# Hypnos_V3.net
KiCad netlist of a schematic drawn in EAGLE
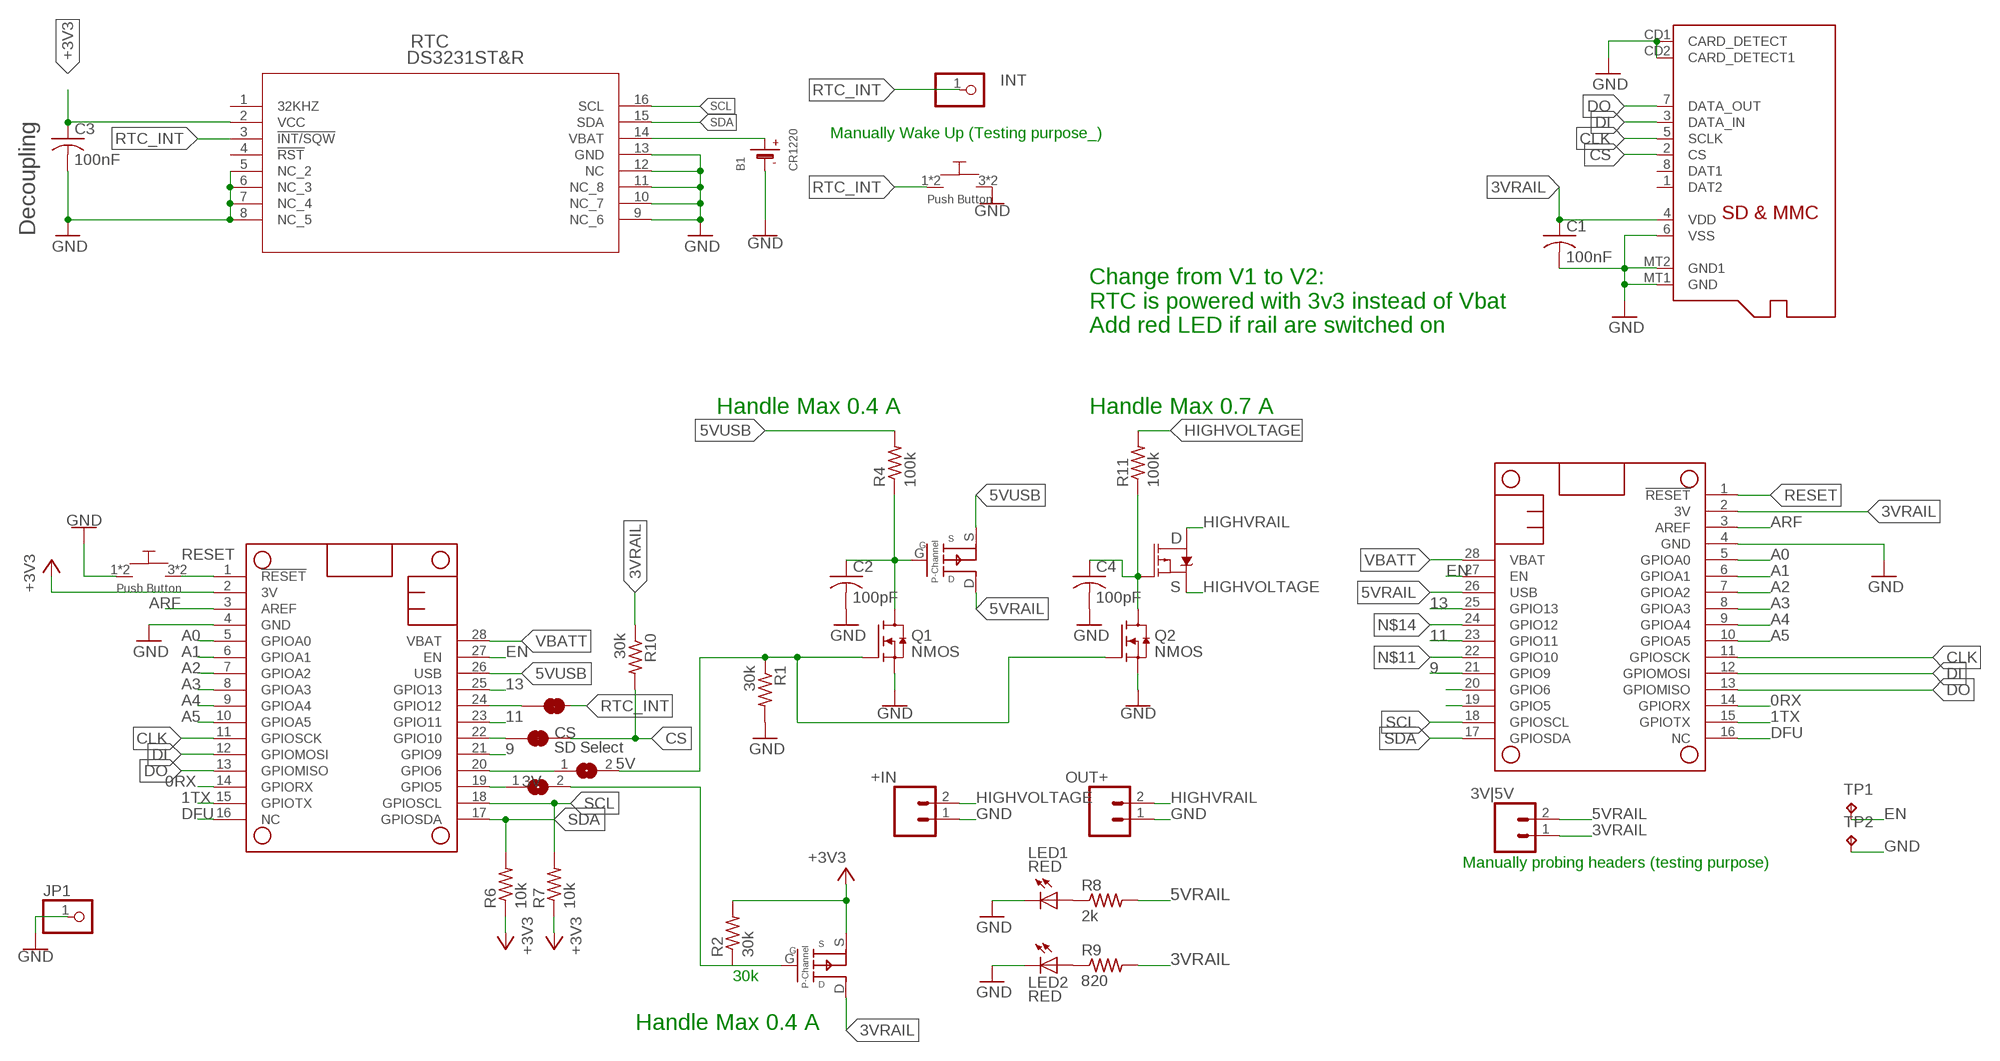
[diagram p0: schematic, sheet 1]

(export (version "E")
  (design (tool "Eeschema 10.0.6"))
  (components
    (comp (ref "+IN")
      (value "HIGHV-IN")
      (footprint "eagle-import:1X02_NO_SILK")
      (libsource (lib "eagle-import") (part "CONN_021X02_NO_SILK"))
    )
    (comp (ref "3V") (value "SJ") (footprint "eagle-import:SJ") (libsource (lib "eagle-import") (part "SJ")))
    (comp (ref "3V|5V")
      (value "CONN_021X02_NO_SILK")
      (footprint "eagle-import:1X02_NO_SILK")
      (libsource (lib "eagle-import") (part "CONN_021X02_NO_SILK"))
    )
    (comp (ref "5V") (value "SJ") (footprint "eagle-import:SJ") (libsource (lib "eagle-import") (part "SJ")))
    (comp (ref "B1")
      (value "CR1220")
      (footprint "eagle-import:CR1220")
      (libsource (lib "eagle-import") (part "BATTERYCR1220_SMT"))
    )
    (comp (ref "C1")
      (value "100nF")
      (footprint "eagle-import:C1206")
      (libsource (lib "eagle-import") (part "C-USC1206"))
    )
    (comp (ref "C2")
      (value "100pF")
      (footprint "eagle-import:C0805")
      (libsource (lib "eagle-import") (part "resistor_348_C-USC0805"))
    )
    (comp (ref "C3")
      (value "100nF")
      (footprint "eagle-import:C1206")
      (libsource (lib "eagle-import") (part "C-USC1206"))
    )
    (comp (ref "C4")
      (value "100pF")
      (footprint "eagle-import:C0805")
      (libsource (lib "eagle-import") (part "resistor_348_C-USC0805"))
    )
    (comp (ref "CS")
      (value "SD Select")
      (footprint "eagle-import:SMT-JUMPER_2_NC_TRACE_SILK")
      (libsource (lib "eagle-import") (part "JUMPER-SMT_2_NC_TRACE_SILK"))
    )
    (comp (ref "INT")
      (value "PINHD-1X1CB")
      (footprint "eagle-import:1X01-CLEANBIG")
      (libsource (lib "eagle-import") (part "PINHD-1X1CB"))
    )
    (comp (ref "JP1")
      (value "PINHD-1X1CB")
      (footprint "eagle-import:1X01-CLEANBIG")
      (libsource (lib "eagle-import") (part "PINHD-1X1CB"))
    )
    (comp (ref "LED1")
      (value "RED")
      (footprint "eagle-import:CHIPLED_0805")
      (libsource (lib "eagle-import") (part "LEDCHIPLED_0805"))
    )
    (comp (ref "LED2")
      (value "RED")
      (footprint "eagle-import:CHIPLED_0805")
      (libsource (lib "eagle-import") (part "LEDCHIPLED_0805"))
    )
    (comp (ref "MICROSD")
      (value "MICROSD")
      (footprint "eagle-import:MICROSD")
      (libsource (lib "eagle-import") (part "MICROSD"))
    )
    (comp (ref "MS1")
      (value "FEATHERWING")
      (footprint "eagle-import:FEATHERWING")
      (libsource (lib "eagle-import") (part "powerboard_FEATHERWING"))
    )
    (comp (ref "MS2")
      (value "FEATHERWING")
      (footprint "eagle-import:FEATHERWING")
      (libsource (lib "eagle-import") (part "FEATHERWING"))
    )
    (comp (ref "OUT+")
      (value "HIGHV-OUT")
      (footprint "eagle-import:1X02_NO_SILK")
      (libsource (lib "eagle-import") (part "CONN_021X02_NO_SILK"))
    )
    (comp (ref "PMOS1")
      (value "SSM3J3228R")
      (footprint "eagle-import:SOT-23-3")
      (libsource (lib "eagle-import") (part "SSM3J3228R"))
    )
    (comp (ref "PMOS2")
      (value "SSM3J3228R")
      (footprint "eagle-import:SOT-23-3")
      (libsource (lib "eagle-import") (part "SSM3J3228R"))
    )
    (comp (ref "PMOS3")
      (value "P-MOSFET")
      (footprint "eagle-import:SOT23-6")
      (libsource (lib "eagle-import") (part "P-MOSFET"))
    )
    (comp (ref "Q1")
      (value "NMOS")
      (footprint "eagle-import:SOT23-S")
      (libsource (lib "eagle-import") (part "NMOS"))
    )
    (comp (ref "Q2")
      (value "NMOS")
      (footprint "eagle-import:SOT23-S")
      (libsource (lib "eagle-import") (part "NMOS"))
    )
    (comp (ref "R1")
      (value "30k")
      (footprint "eagle-import:RES_1206")
      (fields
        (field (name "DIGIKEY_PART_NUMBER") "WSLP-.05TR-ND")
        (field (name "MANUFACTURER") "Vishay Dale")
        (field (name "MPN") "WSLP1206R0500FEA")
        (field (name "CREATED_BY") "PCBLayout.com")
      )
      (libsource (lib "eagle-import") (part "WSLP1206R0500FEA"))
    )
    (comp (ref "R2")
      (value "30k")
      (footprint "eagle-import:RES_1206")
      (fields
        (field (name "DIGIKEY_PART_NUMBER") "WSLP-.05TR-ND")
        (field (name "MANUFACTURER") "Vishay Dale")
        (field (name "MPN") "WSLP1206R0500FEA")
        (field (name "CREATED_BY") "PCBLayout.com")
      )
      (libsource (lib "eagle-import") (part "WSLP1206R0500FEA"))
    )
    (comp (ref "R4")
      (value "100k")
      (footprint "eagle-import:RES_1206")
      (fields
        (field (name "DIGIKEY_PART_NUMBER") "WSLP-.05TR-ND")
        (field (name "MANUFACTURER") "Vishay Dale")
        (field (name "MPN") "WSLP1206R0500FEA")
        (field (name "CREATED_BY") "PCBLayout.com")
      )
      (libsource (lib "eagle-import") (part "WSLP1206R0500FEA"))
    )
    (comp (ref "R6")
      (value "10k")
      (footprint "eagle-import:RES_1206")
      (fields
        (field (name "DIGIKEY_PART_NUMBER") "WSLP-.05TR-ND")
        (field (name "MANUFACTURER") "Vishay Dale")
        (field (name "MPN") "WSLP1206R0500FEA")
        (field (name "CREATED_BY") "PCBLayout.com")
      )
      (libsource (lib "eagle-import") (part "WSLP1206R0500FEA"))
    )
    (comp (ref "R7")
      (value "10k")
      (footprint "eagle-import:RES_1206")
      (fields
        (field (name "DIGIKEY_PART_NUMBER") "WSLP-.05TR-ND")
        (field (name "MANUFACTURER") "Vishay Dale")
        (field (name "MPN") "WSLP1206R0500FEA")
        (field (name "CREATED_BY") "PCBLayout.com")
      )
      (libsource (lib "eagle-import") (part "WSLP1206R0500FEA"))
    )
    (comp (ref "R8")
      (value "2k")
      (footprint "eagle-import:RES_1206")
      (fields
        (field (name "DIGIKEY_PART_NUMBER") "WSLP-.05TR-ND")
        (field (name "MANUFACTURER") "Vishay Dale")
        (field (name "MPN") "WSLP1206R0500FEA")
        (field (name "CREATED_BY") "PCBLayout.com")
      )
      (libsource (lib "eagle-import") (part "WSLP1206R0500FEA"))
    )
    (comp (ref "R9")
      (value "820")
      (footprint "eagle-import:RES_1206")
      (fields
        (field (name "DIGIKEY_PART_NUMBER") "WSLP-.05TR-ND")
        (field (name "MANUFACTURER") "Vishay Dale")
        (field (name "MPN") "WSLP1206R0500FEA")
        (field (name "CREATED_BY") "PCBLayout.com")
      )
      (libsource (lib "eagle-import") (part "WSLP1206R0500FEA"))
    )
    (comp (ref "R10")
      (value "30k")
      (footprint "eagle-import:RES_1206")
      (fields
        (field (name "DIGIKEY_PART_NUMBER") "WSLP-.05TR-ND")
        (field (name "MANUFACTURER") "Vishay Dale")
        (field (name "MPN") "WSLP1206R0500FEA")
        (field (name "CREATED_BY") "PCBLayout.com")
      )
      (libsource (lib "eagle-import") (part "WSLP1206R0500FEA"))
    )
    (comp (ref "R11")
      (value "100k")
      (footprint "eagle-import:RES_1206")
      (fields
        (field (name "DIGIKEY_PART_NUMBER") "WSLP-.05TR-ND")
        (field (name "MANUFACTURER") "Vishay Dale")
        (field (name "MPN") "WSLP1206R0500FEA")
        (field (name "CREATED_BY") "PCBLayout.com")
      )
      (libsource (lib "eagle-import") (part "WSLP1206R0500FEA"))
    )
    (comp (ref "RTC")
      (value "DS3231ST&R")
      (footprint "eagle-import:21-0042B_16")
      (fields (field (name "MANUFACTURER_PART_NUMBER") "DS3231S#T&R"))
      (libsource (lib "eagle-import") (part "DS3231ST&R"))
    )
    (comp (ref "RTC_INT")
      (value "JUMPER-SMT_2_NC_TRACE_SILK")
      (footprint "eagle-import:SMT-JUMPER_2_NC_TRACE_SILK")
      (libsource (lib "eagle-import") (part "JUMPER-SMT_2_NC_TRACE_SILK"))
    )
    (comp (ref "TP1")
      (value "TPTP16R")
      (footprint "eagle-import:TP16R")
      (libsource (lib "eagle-import") (part "TPTP16R"))
    )
    (comp (ref "TP2")
      (value "TPTP16R")
      (footprint "eagle-import:TP16R")
      (libsource (lib "eagle-import") (part "TPTP16R"))
    )
    (comp (ref "U$1")
      (value "PUSH_BUTTON")
      (footprint "eagle-import:PUSHBUTTON_SMD")
      (libsource (lib "eagle-import") (part "PUSH_BUTTON"))
    )
    (comp (ref "U$2")
      (value "PUSH_BUTTON")
      (footprint "eagle-import:PUSHBUTTON_SMD")
      (libsource (lib "eagle-import") (part "PUSH_BUTTON"))
    )
  )
  (nets
    (net (code "1") (name "+3V3") (class "Default")
      (node (ref "C3") (pin "1") (pinfunction "1_1") (pintype "passive"))
      (node (ref "MS2") (pin "2") (pinfunction "3V_2") (pintype "power_in"))
      (node (ref "PMOS2") (pin "S") (pinfunction "S_S") (pintype "bidirectional"))
      (node (ref "R2") (pin "2") (pinfunction "2_2") (pintype "passive"))
      (node (ref "R6") (pin "1") (pinfunction "1_1") (pintype "passive"))
      (node (ref "R7") (pin "1") (pinfunction "1_1") (pintype "passive"))
      (node (ref "RTC") (pin "2") (pinfunction "VCC_2") (pintype "power_in"))
    )
    (net (code "2") (name "/0RX") (class "Default")
      (node (ref "MS1") (pin "14") (pinfunction "GPIORX_14") (pintype "bidirectional"))
      (node (ref "MS2") (pin "14") (pinfunction "GPIORX_14") (pintype "bidirectional"))
    )
    (net (code "3") (name "/1TX") (class "Default")
      (node (ref "MS1") (pin "15") (pinfunction "GPIOTX_15") (pintype "bidirectional"))
      (node (ref "MS2") (pin "15") (pinfunction "GPIOTX_15") (pintype "bidirectional"))
    )
    (net (code "4") (name "/9") (class "Default")
      (node (ref "MS1") (pin "21") (pinfunction "GPIO9_21") (pintype "bidirectional"))
      (node (ref "MS2") (pin "21") (pinfunction "GPIO9_21") (pintype "bidirectional"))
    )
    (net (code "5") (name "/11") (class "Default")
      (node (ref "MS1") (pin "23") (pinfunction "GPIO11_23") (pintype "bidirectional"))
      (node (ref "MS2") (pin "23") (pinfunction "GPIO11_23") (pintype "bidirectional"))
    )
    (net (code "6") (name "/13") (class "Default")
      (node (ref "MS1") (pin "25") (pinfunction "GPIO13_25") (pintype "bidirectional"))
      (node (ref "MS2") (pin "25") (pinfunction "GPIO13_25") (pintype "bidirectional"))
    )
    (net (code "7") (name "/A0") (class "Default")
      (node (ref "MS1") (pin "5") (pinfunction "GPIOA0_5") (pintype "bidirectional"))
      (node (ref "MS2") (pin "5") (pinfunction "GPIOA0_5") (pintype "bidirectional"))
    )
    (net (code "8") (name "/A1") (class "Default")
      (node (ref "MS1") (pin "6") (pinfunction "GPIOA1_6") (pintype "bidirectional"))
      (node (ref "MS2") (pin "6") (pinfunction "GPIOA1_6") (pintype "bidirectional"))
    )
    (net (code "9") (name "/A2") (class "Default")
      (node (ref "MS1") (pin "7") (pinfunction "GPIOA2_7") (pintype "bidirectional"))
      (node (ref "MS2") (pin "7") (pinfunction "GPIOA2_7") (pintype "bidirectional"))
    )
    (net (code "10") (name "/A3") (class "Default")
      (node (ref "MS1") (pin "8") (pinfunction "GPIOA3_8") (pintype "bidirectional"))
      (node (ref "MS2") (pin "8") (pinfunction "GPIOA3_8") (pintype "bidirectional"))
    )
    (net (code "11") (name "/A4") (class "Default")
      (node (ref "MS1") (pin "9") (pinfunction "GPIOA4_9") (pintype "bidirectional"))
      (node (ref "MS2") (pin "9") (pinfunction "GPIOA4_9") (pintype "bidirectional"))
    )
    (net (code "12") (name "/A5") (class "Default")
      (node (ref "MS1") (pin "10") (pinfunction "GPIOA5_10") (pintype "bidirectional"))
      (node (ref "MS2") (pin "10") (pinfunction "GPIOA5_10") (pintype "bidirectional"))
    )
    (net (code "13") (name "/ARF") (class "Default")
      (node (ref "MS1") (pin "3") (pinfunction "AREF_3") (pintype "passive"))
      (node (ref "MS2") (pin "3") (pinfunction "AREF_3") (pintype "passive"))
    )
    (net (code "14") (name "/DFU") (class "Default")
      (node (ref "MS1") (pin "16") (pinfunction "NC_16") (pintype "passive"))
      (node (ref "MS2") (pin "16") (pinfunction "NC_16") (pintype "passive"))
    )
    (net (code "15") (name "/EN") (class "Default")
      (node (ref "MS1") (pin "27") (pinfunction "EN_27") (pintype "passive"))
      (node (ref "MS2") (pin "27") (pinfunction "EN_27") (pintype "passive"))
      (node (ref "TP1") (pin "TP") (pinfunction "TP_TP") (pintype "input"))
    )
    (net (code "16") (name "/HIGHVRAIL") (class "Default")
      (node (ref "OUT+") (pin "2") (pinfunction "2_2") (pintype "passive"))
      (node (ref "PMOS3") (pin "1") (pinfunction "D_1") (pintype "bidirectional"))
      (node (ref "PMOS3") (pin "2") (pinfunction "D_2") (pintype "bidirectional"))
      (node (ref "PMOS3") (pin "5") (pinfunction "D_5") (pintype "bidirectional"))
      (node (ref "PMOS3") (pin "6") (pinfunction "D_6") (pintype "bidirectional"))
    )
    (net (code "17") (name "3VRAIL") (class "Default")
      (node (ref "3V|5V") (pin "1") (pinfunction "1_1") (pintype "passive"))
      (node (ref "C1") (pin "1") (pinfunction "1_1") (pintype "passive"))
      (node (ref "MICROSD") (pin "4") (pinfunction "VDD_4") (pintype "power_in"))
      (node (ref "MS1") (pin "2") (pinfunction "3V_2") (pintype "power_in"))
      (node (ref "PMOS2") (pin "D") (pinfunction "D_D") (pintype "bidirectional"))
      (node (ref "R10") (pin "1") (pinfunction "1_1") (pintype "passive"))
      (node (ref "R9") (pin "2") (pinfunction "2_2") (pintype "passive"))
    )
    (net (code "18") (name "5VRAIL") (class "Default")
      (node (ref "3V|5V") (pin "2") (pinfunction "2_2") (pintype "passive"))
      (node (ref "MS1") (pin "26") (pinfunction "USB_26") (pintype "power_in"))
      (node (ref "PMOS1") (pin "D") (pinfunction "D_D") (pintype "bidirectional"))
      (node (ref "R8") (pin "2") (pinfunction "2_2") (pintype "passive"))
    )
    (net (code "19") (name "5VUSB") (class "Default")
      (node (ref "MS2") (pin "26") (pinfunction "USB_26") (pintype "power_in"))
      (node (ref "PMOS1") (pin "S") (pinfunction "S_S") (pintype "bidirectional"))
      (node (ref "R4") (pin "2") (pinfunction "2_2") (pintype "passive"))
    )
    (net (code "20") (name "CLK") (class "Default")
      (node (ref "MICROSD") (pin "5") (pinfunction "SCLK_5") (pintype "input"))
      (node (ref "MS1") (pin "11") (pinfunction "GPIOSCK_11") (pintype "bidirectional"))
      (node (ref "MS2") (pin "11") (pinfunction "GPIOSCK_11") (pintype "bidirectional"))
    )
    (net (code "21") (name "CS") (class "Default")
      (node (ref "CS") (pin "2") (pinfunction "2_2") (pintype "passive"))
      (node (ref "MICROSD") (pin "2") (pinfunction "CS_2") (pintype "input"))
      (node (ref "R10") (pin "2") (pinfunction "2_2") (pintype "passive"))
    )
    (net (code "22") (name "DI") (class "Default")
      (node (ref "MICROSD") (pin "3") (pinfunction "DATA_IN_3") (pintype "input"))
      (node (ref "MS1") (pin "12") (pinfunction "GPIOMOSI_12") (pintype "bidirectional"))
      (node (ref "MS2") (pin "12") (pinfunction "GPIOMOSI_12") (pintype "bidirectional"))
    )
    (net (code "23") (name "DO") (class "Default")
      (node (ref "MICROSD") (pin "7") (pinfunction "DATA_OUT_7") (pintype "output"))
      (node (ref "MS1") (pin "13") (pinfunction "GPIOMISO_13") (pintype "bidirectional"))
      (node (ref "MS2") (pin "13") (pinfunction "GPIOMISO_13") (pintype "bidirectional"))
    )
    (net (code "24") (name "GND") (class "Default")
      (node (ref "+IN") (pin "1") (pinfunction "1_1") (pintype "passive"))
      (node (ref "B1") (pin "-") (pinfunction "-_-") (pintype "passive"))
      (node (ref "C1") (pin "2") (pinfunction "2_2") (pintype "passive"))
      (node (ref "C2") (pin "2") (pinfunction "2_2") (pintype "passive"))
      (node (ref "C3") (pin "2") (pinfunction "2_2") (pintype "passive"))
      (node (ref "C4") (pin "2") (pinfunction "2_2") (pintype "passive"))
      (node (ref "JP1") (pin "1") (pinfunction "1_1") (pintype "passive"))
      (node (ref "LED1") (pin "C") (pinfunction "C_C") (pintype "passive"))
      (node (ref "LED2") (pin "C") (pinfunction "C_C") (pintype "passive"))
      (node (ref "MICROSD") (pin "6") (pinfunction "VSS_6") (pintype "power_in"))
      (node (ref "MICROSD") (pin "CD1") (pinfunction "CARD_DETECT_CD1") (pintype "passive"))
      (node (ref "MICROSD") (pin "CD2") (pinfunction "CARD_DETECT1_CD2") (pintype "passive"))
      (node (ref "MICROSD") (pin "MT1") (pinfunction "GND_MT1") (pintype "power_in"))
      (node (ref "MICROSD") (pin "MT2") (pinfunction "GND1_MT2") (pintype "power_in"))
      (node (ref "MS1") (pin "4") (pinfunction "GND_4") (pintype "power_in"))
      (node (ref "MS2") (pin "4") (pinfunction "GND_4") (pintype "power_in"))
      (node (ref "OUT+") (pin "1") (pinfunction "1_1") (pintype "passive"))
      (node (ref "Q1") (pin "2") (pinfunction "S_2") (pintype "passive"))
      (node (ref "Q2") (pin "2") (pinfunction "S_2") (pintype "passive"))
      (node (ref "R1") (pin "2") (pinfunction "2_2") (pintype "passive"))
      (node (ref "RTC") (pin "10") (pinfunction "NC_7_10") (pintype "passive"))
      (node (ref "RTC") (pin "11") (pinfunction "NC_8_11") (pintype "passive"))
      (node (ref "RTC") (pin "12") (pinfunction "NC_12") (pintype "passive"))
      (node (ref "RTC") (pin "13") (pinfunction "GND_13") (pintype "power_in"))
      (node (ref "RTC") (pin "5") (pinfunction "NC_2_5") (pintype "passive"))
      (node (ref "RTC") (pin "6") (pinfunction "NC_3_6") (pintype "passive"))
      (node (ref "RTC") (pin "7") (pinfunction "NC_4_7") (pintype "passive"))
      (node (ref "RTC") (pin "8") (pinfunction "NC_5_8") (pintype "passive"))
      (node (ref "RTC") (pin "9") (pinfunction "NC_6_9") (pintype "passive"))
      (node (ref "TP2") (pin "TP") (pinfunction "TP_TP") (pintype "input"))
      (node (ref "U$1") (pin "1") (pinfunction "P$1_1") (pintype "bidirectional"))
      (node (ref "U$1") (pin "2") (pinfunction "P$1_2") (pintype "bidirectional"))
      (node (ref "U$2") (pin "3") (pinfunction "P$2_3") (pintype "bidirectional"))
      (node (ref "U$2") (pin "4") (pinfunction "P$2_4") (pintype "bidirectional"))
    )
    (net (code "25") (name "HIGHVOLTAGE") (class "Default")
      (node (ref "+IN") (pin "2") (pinfunction "2_2") (pintype "passive"))
      (node (ref "PMOS3") (pin "4") (pinfunction "S_4") (pintype "bidirectional"))
      (node (ref "R11") (pin "2") (pinfunction "2_2") (pintype "passive"))
    )
    (net (code "26") (name "N$11") (class "Default")
      (node (ref "CS") (pin "1") (pinfunction "1_1") (pintype "passive"))
      (node (ref "MS1") (pin "22") (pinfunction "GPIO10_22") (pintype "bidirectional"))
      (node (ref "MS2") (pin "22") (pinfunction "GPIO10_22") (pintype "bidirectional"))
    )
    (net (code "27") (name "N$14") (class "Default")
      (node (ref "MS1") (pin "24") (pinfunction "GPIO12_24") (pintype "bidirectional"))
      (node (ref "MS2") (pin "24") (pinfunction "GPIO12_24") (pintype "bidirectional"))
      (node (ref "RTC_INT") (pin "1") (pinfunction "1_1") (pintype "passive"))
    )
    (net (code "28") (name "Net-(3V-Pad2)") (class "Default")
      (node (ref "3V") (pin "2") (pinfunction "2_2") (pintype "passive"))
      (node (ref "PMOS2") (pin "G") (pinfunction "G_G") (pintype "bidirectional"))
      (node (ref "R2") (pin "1") (pinfunction "1_1") (pintype "passive"))
    )
    (net (code "29") (name "Net-(B1-+)") (class "Default")
      (node (ref "B1") (pin "+$1") (pinfunction "+_+$1") (pintype "passive"))
      (node (ref "RTC") (pin "14") (pinfunction "VBAT_14") (pintype "power_in"))
    )
    (net (code "30") (name "Net-(LED1-PadA)") (class "Default")
      (node (ref "LED1") (pin "A") (pinfunction "A_A") (pintype "passive"))
      (node (ref "R8") (pin "1") (pinfunction "1_1") (pintype "passive"))
    )
    (net (code "31") (name "Net-(LED2-PadA)") (class "Default")
      (node (ref "LED2") (pin "A") (pinfunction "A_A") (pintype "passive"))
      (node (ref "R9") (pin "1") (pinfunction "1_1") (pintype "passive"))
    )
    (net (code "32") (name "Net-(MS2-GPIO5)") (class "Default")
      (node (ref "3V") (pin "1") (pinfunction "1_1") (pintype "passive"))
      (node (ref "MS2") (pin "19") (pinfunction "GPIO5_19") (pintype "bidirectional"))
    )
    (net (code "33") (name "Net-(MS2-GPIO6)") (class "Default")
      (node (ref "5V") (pin "1") (pinfunction "1_1") (pintype "passive"))
      (node (ref "MS2") (pin "20") (pinfunction "GPIO6_20") (pintype "bidirectional"))
    )
    (net (code "34") (name "Net-(PMOS3-G)") (class "Default")
      (node (ref "C4") (pin "1") (pinfunction "1_1") (pintype "passive"))
      (node (ref "PMOS3") (pin "3") (pinfunction "G_3") (pintype "bidirectional"))
      (node (ref "Q2") (pin "3") (pinfunction "D_3") (pintype "passive"))
      (node (ref "R11") (pin "1") (pinfunction "1_1") (pintype "passive"))
    )
    (net (code "35") (name "Net-(Q1-D)") (class "Default")
      (node (ref "C2") (pin "1") (pinfunction "1_1") (pintype "passive"))
      (node (ref "PMOS1") (pin "G") (pinfunction "G_G") (pintype "bidirectional"))
      (node (ref "Q1") (pin "3") (pinfunction "D_3") (pintype "passive"))
      (node (ref "R4") (pin "1") (pinfunction "1_1") (pintype "passive"))
    )
    (net (code "36") (name "Net-(Q1-G)") (class "Default")
      (node (ref "5V") (pin "2") (pinfunction "2_2") (pintype "passive"))
      (node (ref "Q1") (pin "1") (pinfunction "G_1") (pintype "passive"))
      (node (ref "Q2") (pin "1") (pinfunction "G_1") (pintype "passive"))
      (node (ref "R1") (pin "1") (pinfunction "1_1") (pintype "passive"))
    )
    (net (code "37") (name "RESET") (class "Default")
      (node (ref "MS1") (pin "1") (pinfunction "~{RESET}_1") (pintype "input"))
      (node (ref "MS2") (pin "1") (pinfunction "~{RESET}_1") (pintype "input"))
      (node (ref "U$1") (pin "3") (pinfunction "P$2_3") (pintype "bidirectional"))
      (node (ref "U$1") (pin "4") (pinfunction "P$2_4") (pintype "bidirectional"))
    )
    (net (code "38") (name "RTC_INT") (class "Default")
      (node (ref "INT") (pin "1") (pinfunction "1_1") (pintype "passive"))
      (node (ref "RTC") (pin "3") (pinfunction "~{INT/SQW}_3") (pintype "passive"))
      (node (ref "RTC_INT") (pin "2") (pinfunction "2_2") (pintype "passive"))
      (node (ref "U$2") (pin "1") (pinfunction "P$1_1") (pintype "bidirectional"))
      (node (ref "U$2") (pin "2") (pinfunction "P$1_2") (pintype "bidirectional"))
    )
    (net (code "39") (name "SCL") (class "Default")
      (node (ref "MS1") (pin "18") (pinfunction "GPIOSCL_18") (pintype "bidirectional"))
      (node (ref "MS2") (pin "18") (pinfunction "GPIOSCL_18") (pintype "bidirectional"))
      (node (ref "R7") (pin "2") (pinfunction "2_2") (pintype "passive"))
      (node (ref "RTC") (pin "16") (pinfunction "SCL_16") (pintype "passive"))
    )
    (net (code "40") (name "SDA") (class "Default")
      (node (ref "MS1") (pin "17") (pinfunction "GPIOSDA_17") (pintype "bidirectional"))
      (node (ref "MS2") (pin "17") (pinfunction "GPIOSDA_17") (pintype "bidirectional"))
      (node (ref "R6") (pin "2") (pinfunction "2_2") (pintype "passive"))
      (node (ref "RTC") (pin "15") (pinfunction "SDA_15") (pintype "passive"))
    )
    (net (code "41") (name "VBATT") (class "Default")
      (node (ref "MS1") (pin "28") (pinfunction "VBAT_28") (pintype "power_in"))
      (node (ref "MS2") (pin "28") (pinfunction "VBAT_28") (pintype "power_in"))
    )
    (net (code "42") (name "unconnected-(MICROSD-DAT1-Pad8)") (class "Default")
      (node (ref "MICROSD") (pin "8") (pinfunction "DAT1_8") (pintype "bidirectional"))
    )
    (net (code "43") (name "unconnected-(MICROSD-DAT2-Pad1)") (class "Default")
      (node (ref "MICROSD") (pin "1") (pinfunction "DAT2_1") (pintype "bidirectional"))
    )
    (net (code "44") (name "unconnected-(MS1-GPIO5-Pad19)") (class "Default")
      (node (ref "MS1") (pin "19") (pinfunction "GPIO5_19") (pintype "bidirectional"))
    )
    (net (code "45") (name "unconnected-(MS1-GPIO6-Pad20)") (class "Default")
      (node (ref "MS1") (pin "20") (pinfunction "GPIO6_20") (pintype "bidirectional"))
    )
    (net (code "46") (name "unconnected-(RTC-32KHZ-Pad1)") (class "Default")
      (node (ref "RTC") (pin "1") (pinfunction "32KHZ_1") (pintype "passive"))
    )
    (net (code "47") (name "unconnected-(RTC-~{RST}-Pad4)") (class "Default")
      (node (ref "RTC") (pin "4") (pinfunction "~{RST}_4") (pintype "passive"))
    )
  )
)
